# Chanal.net
KiCad netlist of a schematic drawn in Altium Designer
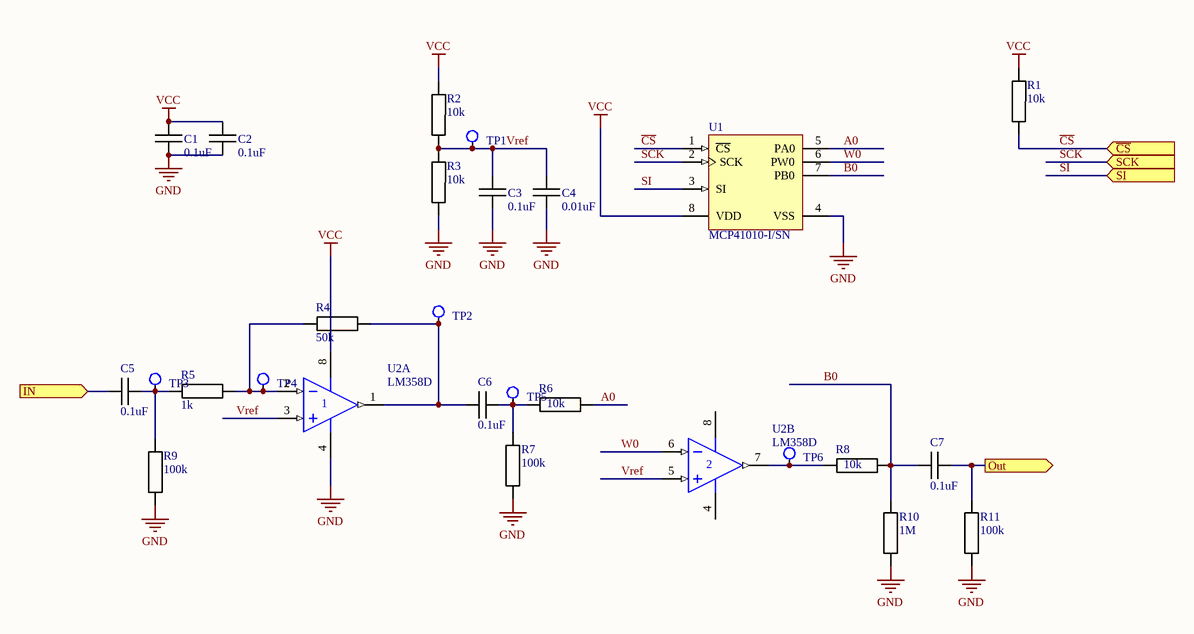
[diagram p0: Chanal.SchDoc]

(export (version "E")
  (design (tool "Eeschema 10.0.6"))
  (components
    (comp (ref "C1") (value "0.1uF") (footprint "SMD 0603") (libsource (lib "Maks_lib") (part "Capasitor")))
    (comp (ref "C2") (value "0.1uF") (footprint "SMD 0603") (libsource (lib "Maks_lib") (part "Capasitor")))
    (comp (ref "C3") (value "0.1uF") (footprint "SMD 0603") (libsource (lib "Maks_lib") (part "Capasitor")))
    (comp (ref "C4") (value "0.01uF") (footprint "SMD 0603") (libsource (lib "Maks_lib") (part "Capasitor")))
    (comp (ref "C5") (value "0.1uF") (footprint "SMD 0603") (libsource (lib "Maks_lib") (part "Capasitor")))
    (comp (ref "C6") (value "0.1uF") (footprint "SMD 0603") (libsource (lib "Maks_lib") (part "Capasitor")))
    (comp (ref "C7") (value "0.1uF") (footprint "SMD 0603") (libsource (lib "Maks_lib") (part "Capasitor")))
    (comp (ref "R1") (value "10k") (footprint "SMD 0603") (libsource (lib "Maks_lib") (part "Resistor")))
    (comp (ref "R2") (value "10k") (footprint "SMD 0603") (libsource (lib "Maks_lib") (part "Resistor")))
    (comp (ref "R3") (value "10k") (footprint "SMD 0603") (libsource (lib "Maks_lib") (part "Resistor")))
    (comp (ref "R4") (value "50k") (footprint "SMD 0603") (libsource (lib "Maks_lib") (part "Resistor")))
    (comp (ref "R5") (value "1k") (footprint "SMD 0603") (libsource (lib "Maks_lib") (part "Resistor")))
    (comp (ref "R6") (value "10k") (footprint "SMD 0603") (libsource (lib "Maks_lib") (part "Resistor")))
    (comp (ref "R7") (value "100k") (footprint "SMD 0603") (libsource (lib "Maks_lib") (part "Resistor")))
    (comp (ref "R8") (value "10k") (footprint "SMD 0603") (libsource (lib "Maks_lib") (part "Resistor")))
    (comp (ref "R9") (value "100k") (footprint "SMD 0603") (libsource (lib "Maks_lib") (part "Resistor")))
    (comp (ref "R10") (value "1M") (footprint "SMD 0603") (libsource (lib "Maks_lib") (part "Resistor")))
    (comp (ref "R11") (value "100k") (footprint "SMD 0603") (libsource (lib "Maks_lib") (part "Resistor")))
    (comp (ref "TP1")
      (value "testPoint")
      (footprint "TESTPOINT")
      (libsource (lib "Maks_lib") (part "TestPoint"))
    )
    (comp (ref "TP2")
      (value "testPoint")
      (footprint "TESTPOINT")
      (libsource (lib "Maks_lib") (part "TestPoint"))
    )
    (comp (ref "TP3")
      (value "testPoint")
      (footprint "TESTPOINT")
      (libsource (lib "Maks_lib") (part "TestPoint"))
    )
    (comp (ref "TP4")
      (value "testPoint")
      (footprint "TESTPOINT")
      (libsource (lib "Maks_lib") (part "TestPoint"))
    )
    (comp (ref "TP5")
      (value "testPoint")
      (footprint "TESTPOINT")
      (libsource (lib "Maks_lib") (part "TestPoint"))
    )
    (comp (ref "TP6")
      (value "testPoint")
      (footprint "TESTPOINT")
      (libsource (lib "Maks_lib") (part "TestPoint"))
    )
    (comp (ref "U1")
      (value "MCP41010-I/SN")
      (footprint "SOIC-SN8_N")
      (description "Single/Dual Digital Potentiometer with SPI Interface, 8-Pin SOIC 150mil, Industrial Temperature")
      (fields (field (name "MANUFACTURER") "Microchip"))
      (libsource (lib "Microchip Mixed Signal") (part "MCP41010-I/SN"))
    )
    (comp (ref "U2")
      (value "LM358D")
      (footprint "751-02_N")
      (description "Dual Low-Power Operational Amplifier")
      (fields (field (name "PUBLISHER") "Altium Limited"))
      (libsource (lib "Motorola Amplifier Operational Amplifier") (part "LM358D"))
    )
  )
  (nets
    (net (code "1") (name "/A0") (class "Default")
      (node (ref "R6") (pin "1") (pinfunction "1_1") (pintype "passive"))
      (node (ref "U1") (pin "5") (pinfunction "PA0_5") (pintype "passive"))
    )
    (net (code "2") (name "/B0") (class "Default")
      (node (ref "C7") (pin "1") (pinfunction "1_1") (pintype "passive"))
      (node (ref "R10") (pin "1") (pinfunction "1_1") (pintype "passive"))
      (node (ref "R8") (pin "1") (pinfunction "1_1") (pintype "passive"))
      (node (ref "U1") (pin "7") (pinfunction "PB0_7") (pintype "passive"))
    )
    (net (code "3") (name "/CS") (class "Default")
      (node (ref "R1") (pin "1") (pinfunction "1_1") (pintype "passive"))
      (node (ref "U1") (pin "1") (pinfunction "~{CS}_1") (pintype "input"))
    )
    (net (code "4") (name "/IN") (class "Default")
      (node (ref "C5") (pin "1") (pinfunction "1_1") (pintype "passive"))
    )
    (net (code "5") (name "/Out") (class "Default")
      (node (ref "C7") (pin "2") (pinfunction "2_2") (pintype "passive"))
      (node (ref "R11") (pin "1") (pinfunction "1_1") (pintype "passive"))
    )
    (net (code "6") (name "/SCK") (class "Default")
      (node (ref "U1") (pin "2") (pinfunction "SCK_2") (pintype "input"))
    )
    (net (code "7") (name "/SI") (class "Default")
      (node (ref "U1") (pin "3") (pinfunction "SI_3") (pintype "input"))
    )
    (net (code "8") (name "/Vref") (class "Default")
      (node (ref "C3") (pin "1") (pinfunction "1_1") (pintype "passive"))
      (node (ref "C4") (pin "1") (pinfunction "1_1") (pintype "passive"))
      (node (ref "R2") (pin "1") (pinfunction "1_1") (pintype "passive"))
      (node (ref "R3") (pin "2") (pinfunction "2_2") (pintype "passive"))
      (node (ref "TP1") (pin "0") (pinfunction "0_0") (pintype "passive"))
      (node (ref "U2") (pin "3") (pinfunction "IN+_3") (pintype "input"))
      (node (ref "U2") (pin "5") (pinfunction "IN+_5") (pintype "input"))
    )
    (net (code "9") (name "/W0") (class "Default")
      (node (ref "U1") (pin "6") (pinfunction "PW0_6") (pintype "passive"))
      (node (ref "U2") (pin "6") (pinfunction "IN-_6") (pintype "input"))
    )
    (net (code "10") (name "GND") (class "Default")
      (node (ref "C1") (pin "2") (pinfunction "2_2") (pintype "passive"))
      (node (ref "C2") (pin "2") (pinfunction "2_2") (pintype "passive"))
      (node (ref "C3") (pin "2") (pinfunction "2_2") (pintype "passive"))
      (node (ref "C4") (pin "2") (pinfunction "2_2") (pintype "passive"))
      (node (ref "R10") (pin "2") (pinfunction "2_2") (pintype "passive"))
      (node (ref "R11") (pin "2") (pinfunction "2_2") (pintype "passive"))
      (node (ref "R3") (pin "1") (pinfunction "1_1") (pintype "passive"))
      (node (ref "R7") (pin "2") (pinfunction "2_2") (pintype "passive"))
      (node (ref "R9") (pin "2") (pinfunction "2_2") (pintype "passive"))
      (node (ref "U1") (pin "4") (pinfunction "VSS_4") (pintype "power_in"))
      (node (ref "U2") (pin "4") (pinfunction "V-_4") (pintype "power_in"))
    )
    (net (code "11") (name "Net-(C5-Pad2)") (class "Default")
      (node (ref "C5") (pin "2") (pinfunction "2_2") (pintype "passive"))
      (node (ref "R5") (pin "2") (pinfunction "2_2") (pintype "passive"))
      (node (ref "R9") (pin "1") (pinfunction "1_1") (pintype "passive"))
      (node (ref "TP3") (pin "0") (pinfunction "0_0") (pintype "passive"))
    )
    (net (code "12") (name "Net-(C6-Pad2)") (class "Default")
      (node (ref "C6") (pin "2") (pinfunction "2_2") (pintype "passive"))
      (node (ref "R6") (pin "2") (pinfunction "2_2") (pintype "passive"))
      (node (ref "R7") (pin "1") (pinfunction "1_1") (pintype "passive"))
      (node (ref "TP5") (pin "0") (pinfunction "0_0") (pintype "passive"))
    )
    (net (code "13") (name "Net-(U2A-IN-)") (class "Default")
      (node (ref "R4") (pin "2") (pinfunction "2_2") (pintype "passive"))
      (node (ref "R5") (pin "1") (pinfunction "1_1") (pintype "passive"))
      (node (ref "TP4") (pin "0") (pinfunction "0_0") (pintype "passive"))
      (node (ref "U2") (pin "2") (pinfunction "IN-_2") (pintype "input"))
    )
    (net (code "14") (name "Net-(U2A-OUT)") (class "Default")
      (node (ref "C6") (pin "1") (pinfunction "1_1") (pintype "passive"))
      (node (ref "R4") (pin "1") (pinfunction "1_1") (pintype "passive"))
      (node (ref "TP2") (pin "0") (pinfunction "0_0") (pintype "passive"))
      (node (ref "U2") (pin "1") (pinfunction "OUT_1") (pintype "output"))
    )
    (net (code "15") (name "Net-(U2B-OUT)") (class "Default")
      (node (ref "R8") (pin "2") (pinfunction "2_2") (pintype "passive"))
      (node (ref "TP6") (pin "0") (pinfunction "0_0") (pintype "passive"))
      (node (ref "U2") (pin "7") (pinfunction "OUT_7") (pintype "output"))
    )
    (net (code "16") (name "VCC") (class "Default")
      (node (ref "C1") (pin "1") (pinfunction "1_1") (pintype "passive"))
      (node (ref "C2") (pin "1") (pinfunction "1_1") (pintype "passive"))
      (node (ref "R1") (pin "2") (pinfunction "2_2") (pintype "passive"))
      (node (ref "R2") (pin "2") (pinfunction "2_2") (pintype "passive"))
      (node (ref "U1") (pin "8") (pinfunction "VDD_8") (pintype "power_in"))
      (node (ref "U2") (pin "8") (pinfunction "V+_8") (pintype "power_in"))
    )
    (net (code "17") (name "unconnected-(U2B-V+-Pad8)") (class "Default")
      (node (ref "U2") (pin "8") (pinfunction "V+_8") (pintype "power_in"))
    )
    (net (code "18") (name "unconnected-(U2B-V--Pad4)") (class "Default")
      (node (ref "U2") (pin "4") (pinfunction "V-_4") (pintype "power_in"))
    )
  )
)
